# LIGHT_MODULE.net
KiCad netlist of a schematic drawn in EAGLE
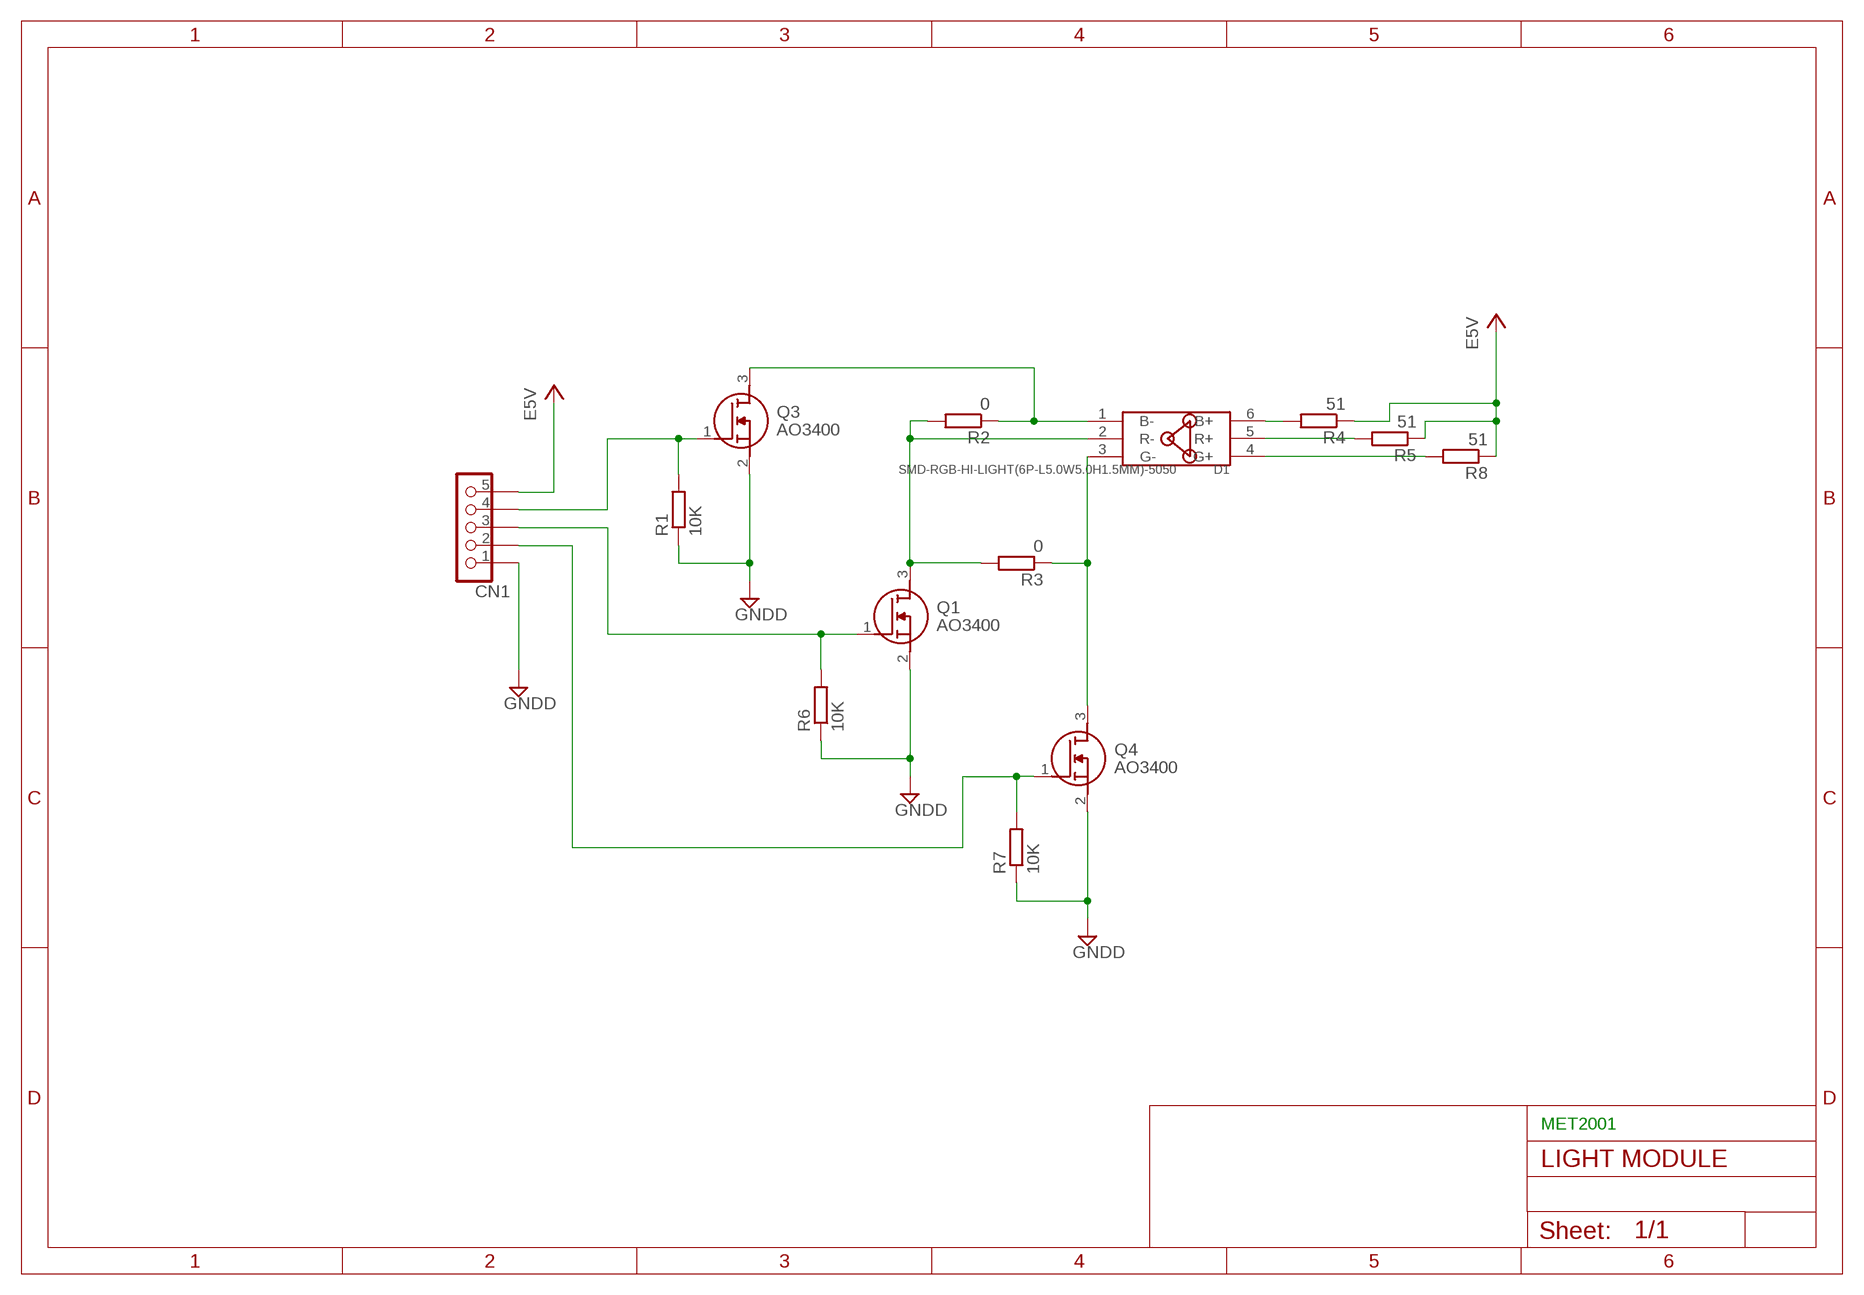
[diagram p0: schematic, sheet 1]

(export (version "E")
  (design (tool "Eeschema 10.0.6"))
  (components
    (comp (ref "CN1")
      (value "HEADER1X5")
      (footprint "eagle-import:HEADER_1X5")
      (libsource (lib "eagle-import") (part "HEADER1X5"))
    )
    (comp (ref "D1")
      (value "SMD-RGB-HI-LIGHT(6P-L5.0W5.0H1.5MM)-5050")
      (footprint "eagle-import:LED6-SMD-5050")
      (fields (field (name "MF") "SparkFun Electronics") (field (name "MP") "5050RGB"))
      (libsource (lib "eagle-import") (part "SMD-RGB-HI-LIGHT(6P-L5.0W5.0H1.5MM)-5050"))
    )
    (comp (ref "Q1")
      (value "AO3400")
      (footprint "eagle-import:SOT95P280X125-3N")
      (libsource (lib "eagle-import") (part "AO3400"))
    )
    (comp (ref "Q3")
      (value "AO3400")
      (footprint "eagle-import:SOT95P280X125-3N")
      (libsource (lib "eagle-import") (part "AO3400"))
    )
    (comp (ref "Q4")
      (value "AO3400")
      (footprint "eagle-import:SOT95P280X125-3N")
      (libsource (lib "eagle-import") (part "AO3400"))
    )
    (comp (ref "R1")
      (value "10K")
      (footprint "eagle-import:R0805")
      (libsource (lib "eagle-import") (part "RES_0805"))
    )
    (comp (ref "R2")
      (value "0")
      (footprint "eagle-import:R0805")
      (libsource (lib "eagle-import") (part "RES_0805"))
    )
    (comp (ref "R3")
      (value "0")
      (footprint "eagle-import:R0805")
      (libsource (lib "eagle-import") (part "RES_0805"))
    )
    (comp (ref "R4")
      (value "51")
      (footprint "eagle-import:R0805")
      (libsource (lib "eagle-import") (part "RES_0805"))
    )
    (comp (ref "R5")
      (value "51")
      (footprint "eagle-import:R0805")
      (libsource (lib "eagle-import") (part "RES_0805"))
    )
    (comp (ref "R6")
      (value "10K")
      (footprint "eagle-import:R0805")
      (libsource (lib "eagle-import") (part "RES_0805"))
    )
    (comp (ref "R7")
      (value "10K")
      (footprint "eagle-import:R0805")
      (libsource (lib "eagle-import") (part "RES_0805"))
    )
    (comp (ref "R8")
      (value "51")
      (footprint "eagle-import:R0805")
      (libsource (lib "eagle-import") (part "RES_0805"))
    )
  )
  (nets
    (net (code "1") (name "E5V") (class "Default")
      (node (ref "CN1") (pin "5") (pinfunction "5_5") (pintype "passive"))
      (node (ref "R4") (pin "1") (pinfunction "1_1") (pintype "passive"))
      (node (ref "R5") (pin "1") (pinfunction "1_1") (pintype "passive"))
      (node (ref "R8") (pin "1") (pinfunction "1_1") (pintype "passive"))
    )
    (net (code "2") (name "GNDD") (class "Default")
      (node (ref "CN1") (pin "1") (pinfunction "1_1") (pintype "passive"))
      (node (ref "Q1") (pin "2") (pinfunction "S_2") (pintype "bidirectional"))
      (node (ref "Q3") (pin "2") (pinfunction "S_2") (pintype "bidirectional"))
      (node (ref "Q4") (pin "2") (pinfunction "S_2") (pintype "bidirectional"))
      (node (ref "R1") (pin "1") (pinfunction "1_1") (pintype "passive"))
      (node (ref "R6") (pin "1") (pinfunction "1_1") (pintype "passive"))
      (node (ref "R7") (pin "1") (pinfunction "1_1") (pintype "passive"))
    )
    (net (code "3") (name "Net-(D1-B+)") (class "Default")
      (node (ref "D1") (pin "6") (pinfunction "B+_6") (pintype "bidirectional"))
      (node (ref "R4") (pin "2") (pinfunction "2_2") (pintype "passive"))
    )
    (net (code "4") (name "Net-(D1-B-)") (class "Default")
      (node (ref "D1") (pin "1") (pinfunction "B-_1") (pintype "bidirectional"))
      (node (ref "Q3") (pin "3") (pinfunction "D_3") (pintype "bidirectional"))
      (node (ref "R2") (pin "1") (pinfunction "1_1") (pintype "passive"))
    )
    (net (code "5") (name "Net-(D1-G+)") (class "Default")
      (node (ref "D1") (pin "4") (pinfunction "G+_4") (pintype "bidirectional"))
      (node (ref "R8") (pin "2") (pinfunction "2_2") (pintype "passive"))
    )
    (net (code "6") (name "Net-(D1-G-)") (class "Default")
      (node (ref "D1") (pin "3") (pinfunction "G-_3") (pintype "bidirectional"))
      (node (ref "Q4") (pin "3") (pinfunction "D_3") (pintype "bidirectional"))
      (node (ref "R3") (pin "1") (pinfunction "1_1") (pintype "passive"))
    )
    (net (code "7") (name "Net-(D1-R+)") (class "Default")
      (node (ref "D1") (pin "5") (pinfunction "R+_5") (pintype "bidirectional"))
      (node (ref "R5") (pin "2") (pinfunction "2_2") (pintype "passive"))
    )
    (net (code "8") (name "Net-(D1-R-)") (class "Default")
      (node (ref "D1") (pin "2") (pinfunction "R-_2") (pintype "bidirectional"))
      (node (ref "Q1") (pin "3") (pinfunction "D_3") (pintype "bidirectional"))
      (node (ref "R2") (pin "2") (pinfunction "2_2") (pintype "passive"))
      (node (ref "R3") (pin "2") (pinfunction "2_2") (pintype "passive"))
    )
    (net (code "9") (name "Net-(Q1-G)") (class "Default")
      (node (ref "CN1") (pin "3") (pinfunction "3_3") (pintype "passive"))
      (node (ref "Q1") (pin "1") (pinfunction "G_1") (pintype "bidirectional"))
      (node (ref "R6") (pin "2") (pinfunction "2_2") (pintype "passive"))
    )
    (net (code "10") (name "Net-(Q3-G)") (class "Default")
      (node (ref "CN1") (pin "4") (pinfunction "4_4") (pintype "passive"))
      (node (ref "Q3") (pin "1") (pinfunction "G_1") (pintype "bidirectional"))
      (node (ref "R1") (pin "2") (pinfunction "2_2") (pintype "passive"))
    )
    (net (code "11") (name "Net-(Q4-G)") (class "Default")
      (node (ref "CN1") (pin "2") (pinfunction "2_2") (pintype "passive"))
      (node (ref "Q4") (pin "1") (pinfunction "G_1") (pintype "bidirectional"))
      (node (ref "R7") (pin "2") (pinfunction "2_2") (pintype "passive"))
    )
  )
)
